# TamaCollar1_Mk1_Schematic_v34_V45.net
KiCad netlist of a schematic drawn in EAGLE
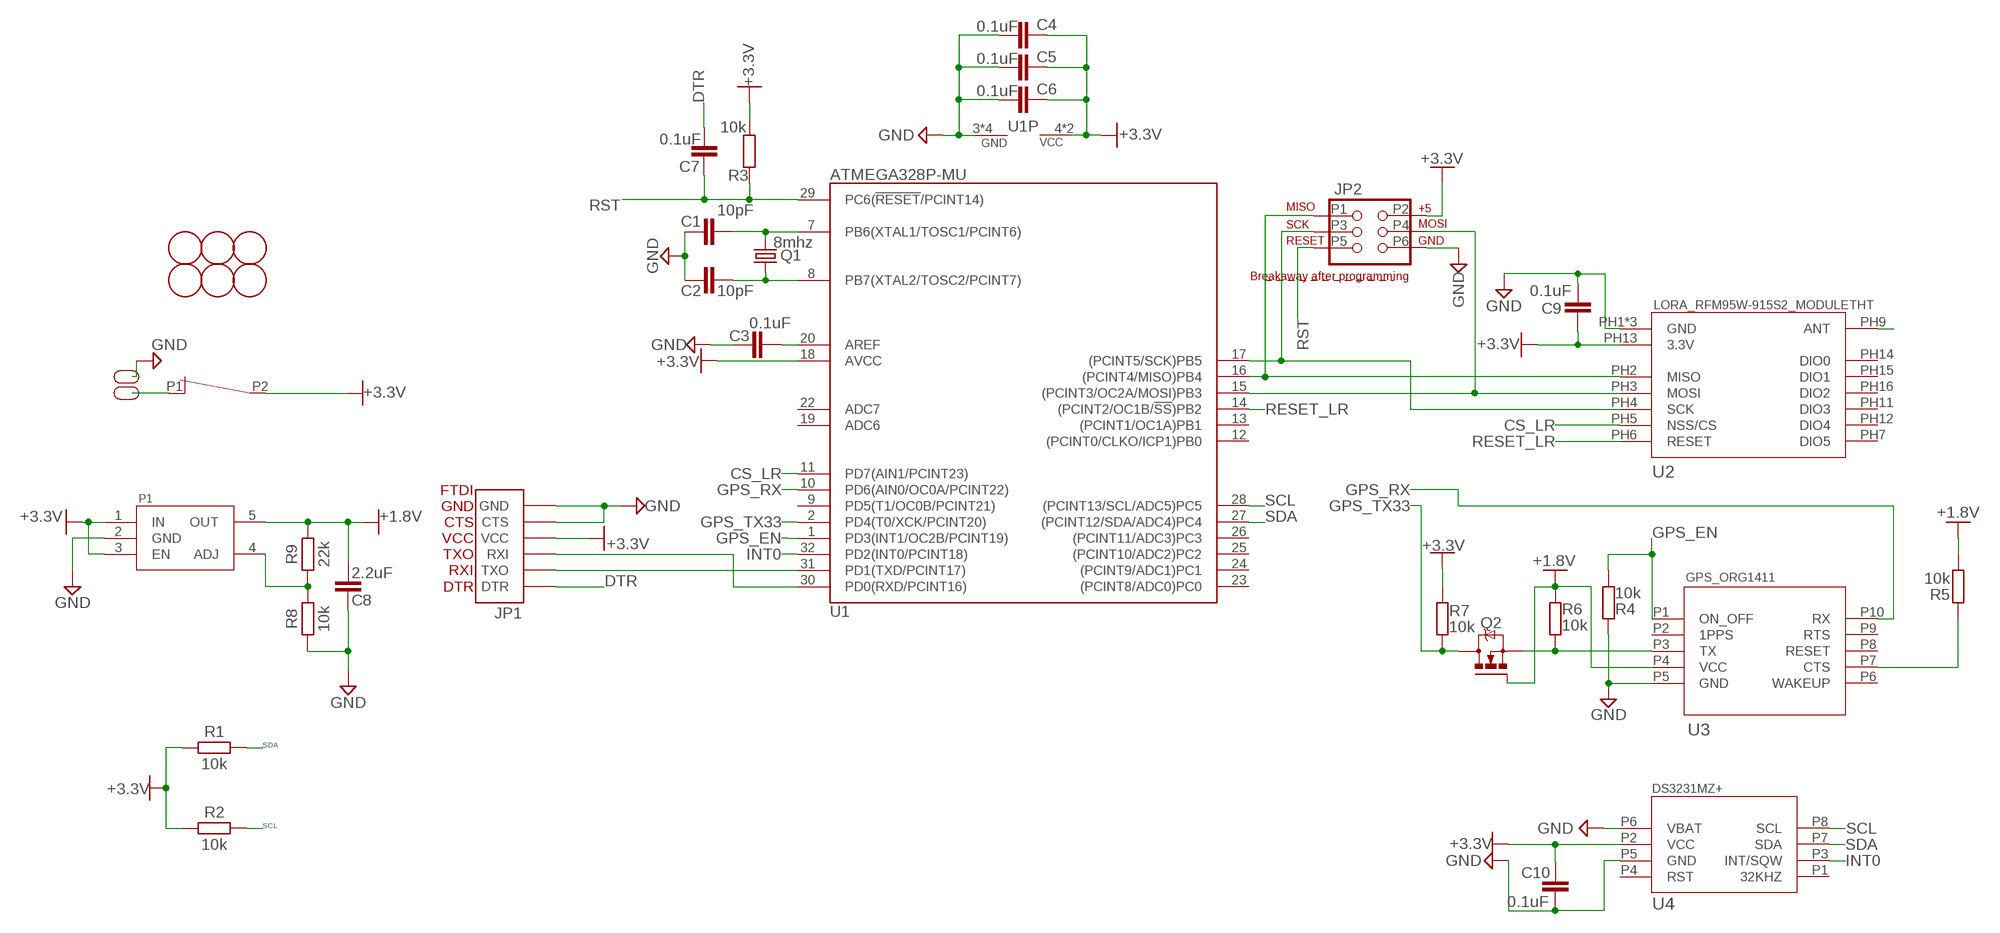
[diagram p0: schematic, sheet 1]

(export (version "E")
  (design (tool "Eeschema 10.0.6"))
  (components
    (comp (ref "BATT+")
      (value "BREAKOUT_PADL")
      (footprint "eagle-import:BREAKOUT_PAD_1_1X2MM")
      (libsource (lib "eagle-import") (part "BREAKOUT_PADL"))
    )
    (comp (ref "BR2")
      (value "MOUSEBITE3X1.25")
      (footprint "eagle-import:MOUSEBITE_3H_6TRACE(1.25MM)")
      (libsource (lib "eagle-import") (part "MOUSEBITE3X1.25"))
    )
    (comp (ref "C1")
      (value "10pF")
      (footprint "eagle-import:CAPC1005X60")
      (libsource (lib "eagle-import") (part "CCHIP-0402(1005-METRIC)_"))
    )
    (comp (ref "C2")
      (value "10pF")
      (footprint "eagle-import:CAPC1005X60")
      (libsource (lib "eagle-import") (part "CCHIP-0402(1005-METRIC)_"))
    )
    (comp (ref "C3")
      (value "0.1uF")
      (footprint "eagle-import:CAPC1005X60")
      (libsource (lib "eagle-import") (part "CCHIP-0402(1005-METRIC)_"))
    )
    (comp (ref "C4")
      (value "0.1uF")
      (footprint "eagle-import:CAPC1005X60")
      (libsource (lib "eagle-import") (part "CCHIP-0402(1005-METRIC)_"))
    )
    (comp (ref "C5")
      (value "0.1uF")
      (footprint "eagle-import:CAPC1005X60")
      (libsource (lib "eagle-import") (part "CCHIP-0402(1005-METRIC)_"))
    )
    (comp (ref "C6")
      (value "0.1uF")
      (footprint "eagle-import:CAPC1005X60")
      (libsource (lib "eagle-import") (part "CCHIP-0402(1005-METRIC)_"))
    )
    (comp (ref "C7")
      (value "0.1uF")
      (footprint "eagle-import:CAPC1005X60")
      (libsource (lib "eagle-import") (part "CCHIP-0402(1005-METRIC)_"))
    )
    (comp (ref "C8")
      (value "2.2uF")
      (footprint "eagle-import:CAPC1005X60")
      (libsource (lib "eagle-import") (part "CCHIP-0402(1005-METRIC)_"))
    )
    (comp (ref "C9")
      (value "0.1uF")
      (footprint "eagle-import:CAPC1005X60")
      (libsource (lib "eagle-import") (part "CCHIP-0402(1005-METRIC)_"))
    )
    (comp (ref "C10")
      (value "0.1uF")
      (footprint "eagle-import:CAPC1005X60")
      (libsource (lib "eagle-import") (part "CCHIP-0402(1005-METRIC)_"))
    )
    (comp (ref "F1")
      (value "FIDUCIAL")
      (footprint "eagle-import:FIDUCIAL_1MM")
      (libsource (lib "eagle-import") (part "FIDUCIAL"))
    )
    (comp (ref "F2")
      (value "FIDUCIAL")
      (footprint "eagle-import:FIDUCIAL_1MM")
      (libsource (lib "eagle-import") (part "FIDUCIAL"))
    )
    (comp (ref "F3")
      (value "FIDUCIAL")
      (footprint "eagle-import:FIDUCIAL_1MM")
      (libsource (lib "eagle-import") (part "FIDUCIAL"))
    )
    (comp (ref "F4")
      (value "FIDUCIAL")
      (footprint "eagle-import:FIDUCIAL_1MM")
      (libsource (lib "eagle-import") (part "FIDUCIAL"))
    )
    (comp (ref "F5")
      (value "FIDUCIAL")
      (footprint "eagle-import:FIDUCIAL_1MM")
      (libsource (lib "eagle-import") (part "FIDUCIAL"))
    )
    (comp (ref "F6")
      (value "FIDUCIAL")
      (footprint "eagle-import:FIDUCIAL_1MM")
      (libsource (lib "eagle-import") (part "FIDUCIAL"))
    )
    (comp (ref "GND")
      (value "BREAKOUT_PADL")
      (footprint "eagle-import:BREAKOUT_PAD_1_1X2MM")
      (libsource (lib "eagle-import") (part "BREAKOUT_PADL"))
    )
    (comp (ref "JP1")
      (value "FTDI_DEVICESMALL")
      (footprint "eagle-import:FTDI_DEVICE_SMD_SMALL")
      (libsource (lib "eagle-import") (part "FTDI_DEVICESMALL"))
    )
    (comp (ref "JP2")
      (value "AVR_SPI_PRG_61X6")
      (footprint "eagle-import:1X6-SMD")
      (libsource (lib "eagle-import") (part "AVR_SPI_PRG_61X6"))
    )
    (comp (ref "P1")
      (value "LDO_MIC5205YM5")
      (footprint "eagle-import:MIC5205")
      (libsource (lib "eagle-import") (part "LDO_MIC5205YM5"))
    )
    (comp (ref "Q1")
      (value "8mhz")
      (footprint "eagle-import:CRYSTAL_NX3225GD")
      (libsource (lib "eagle-import") (part "CRYSTAL"))
    )
    (comp (ref "Q2")
      (value "NMOSFET")
      (footprint "eagle-import:SOT23")
      (libsource (lib "eagle-import") (part "NMOSFETSOT23"))
    )
    (comp (ref "R1")
      (value "10k")
      (footprint "eagle-import:RESC1005X40")
      (libsource (lib "eagle-import") (part "RCHIP-0402(1005-METRIC)_"))
    )
    (comp (ref "R2")
      (value "10k")
      (footprint "eagle-import:RESC1005X40")
      (libsource (lib "eagle-import") (part "RCHIP-0402(1005-METRIC)_"))
    )
    (comp (ref "R3")
      (value "10k")
      (footprint "eagle-import:RESC1005X40")
      (libsource (lib "eagle-import") (part "RCHIP-0402(1005-METRIC)_"))
    )
    (comp (ref "R4")
      (value "10k")
      (footprint "eagle-import:RESC1005X40")
      (libsource (lib "eagle-import") (part "RCHIP-0402(1005-METRIC)_"))
    )
    (comp (ref "R5")
      (value "10k")
      (footprint "eagle-import:RESC1005X40")
      (libsource (lib "eagle-import") (part "RCHIP-0402(1005-METRIC)_"))
    )
    (comp (ref "R6")
      (value "10k")
      (footprint "eagle-import:RESC1005X40")
      (libsource (lib "eagle-import") (part "RCHIP-0402(1005-METRIC)_"))
    )
    (comp (ref "R7")
      (value "10k")
      (footprint "eagle-import:RESC1005X40")
      (libsource (lib "eagle-import") (part "RCHIP-0402(1005-METRIC)_"))
    )
    (comp (ref "R8")
      (value "10k")
      (footprint "eagle-import:RESC1005X40")
      (libsource (lib "eagle-import") (part "RCHIP-0402(1005-METRIC)_"))
    )
    (comp (ref "R9")
      (value "22k")
      (footprint "eagle-import:RESC1005X40")
      (libsource (lib "eagle-import") (part "RCHIP-0402(1005-METRIC)_"))
    )
    (comp (ref "SW1")
      (value "REED_SWITCH")
      (footprint "eagle-import:REED_CT05")
      (libsource (lib "eagle-import") (part "REED_SWITCH"))
    )
    (comp (ref "U1")
      (value "ATMEGA328P-MU")
      (footprint "eagle-import:QFN32_5X5_0.50")
      (fields
        (field (name "LINK") "https://www.rhydolabz.com/components-microcontrollers-c-172_192/atmega328pmu-smd-p-2612.html")
      )
      (libsource (lib "eagle-import") (part "ATMEGA8P-MU32"))
    )
    (comp (ref "U2")
      (value "LORA_RFM95W-915S2_MODULETHT")
      (footprint "eagle-import:LORA_RFM95W-915S2_16STANDOFFMODULE")
      (libsource (lib "eagle-import") (part "LORA_RFM95W-915S2_MODULETHT"))
    )
    (comp (ref "U3")
      (value "GPS_ORG1411")
      (footprint "eagle-import:ORG1411")
      (libsource (lib "eagle-import") (part "GPS_ORG1411"))
    )
    (comp (ref "U4")
      (value "DS3231MZ+")
      (footprint "eagle-import:DS3231MZ+_SOIC8")
      (libsource (lib "eagle-import") (part "DS3231MZ+"))
    )
  )
  (nets
    (net (code "1") (name "+1.8V") (class "Default")
      (node (ref "C8") (pin "2") (pinfunction "2_2") (pintype "passive"))
      (node (ref "P1") (pin "5") (pinfunction "OUT_5") (pintype "bidirectional"))
      (node (ref "Q2") (pin "1") (pinfunction "G_1") (pintype "passive"))
      (node (ref "R5") (pin "1") (pinfunction "1_1") (pintype "passive"))
      (node (ref "R6") (pin "2") (pinfunction "2_2") (pintype "passive"))
      (node (ref "R9") (pin "2") (pinfunction "2_2") (pintype "passive"))
      (node (ref "U3") (pin "P4") (pinfunction "VCC_P4") (pintype "power_in"))
    )
    (net (code "2") (name "+3.3V") (class "Default")
      (node (ref "C10") (pin "1") (pinfunction "1_1") (pintype "passive"))
      (node (ref "C4") (pin "1") (pinfunction "1_1") (pintype "passive"))
      (node (ref "C5") (pin "1") (pinfunction "1_1") (pintype "passive"))
      (node (ref "C6") (pin "1") (pinfunction "1_1") (pintype "passive"))
      (node (ref "C9") (pin "1") (pinfunction "1_1") (pintype "passive"))
      (node (ref "JP1") (pin "P4") (pinfunction "VCC_P4") (pintype "bidirectional"))
      (node (ref "JP2") (pin "P2") (pinfunction "2_P2") (pintype "passive"))
      (node (ref "P1") (pin "1") (pinfunction "IN_1") (pintype "bidirectional"))
      (node (ref "P1") (pin "3") (pinfunction "EN_3") (pintype "bidirectional"))
      (node (ref "R1") (pin "1") (pinfunction "1_1") (pintype "passive"))
      (node (ref "R2") (pin "1") (pinfunction "1_1") (pintype "passive"))
      (node (ref "R3") (pin "1") (pinfunction "1_1") (pintype "passive"))
      (node (ref "R7") (pin "2") (pinfunction "2_2") (pintype "passive"))
      (node (ref "SW1") (pin "P2") (pinfunction "PAD2_P2") (pintype "bidirectional"))
      (node (ref "U1") (pin "18") (pinfunction "AVCC_18") (pintype "power_in"))
      (node (ref "U1") (pin "4") (pinfunction "VCC_4") (pintype "power_in"))
      (node (ref "U1") (pin "6") (pinfunction "VCC_6") (pintype "power_in"))
      (node (ref "U2") (pin "PH13") (pinfunction "3.3V_PH13") (pintype "bidirectional"))
      (node (ref "U4") (pin "P2") (pinfunction "VCC_P2") (pintype "power_in"))
    )
    (net (code "3") (name "/CS_LR") (class "Default")
      (node (ref "U1") (pin "11") (pinfunction "PD7(AIN1/PCINT23)_11") (pintype "bidirectional"))
      (node (ref "U2") (pin "PH5") (pinfunction "NSS/CS_PH5") (pintype "bidirectional"))
    )
    (net (code "4") (name "/DTR") (class "Default")
      (node (ref "C7") (pin "2") (pinfunction "2_2") (pintype "passive"))
      (node (ref "JP1") (pin "P1") (pinfunction "DTR_P1") (pintype "bidirectional"))
    )
    (net (code "5") (name "/GPS_EN") (class "Default")
      (node (ref "R4") (pin "1") (pinfunction "1_1") (pintype "passive"))
      (node (ref "U1") (pin "1") (pinfunction "PD3(INT1/OC2B/PCINT19)_1") (pintype "bidirectional"))
      (node (ref "U3") (pin "P1") (pinfunction "ON_OFF_P1") (pintype "input"))
    )
    (net (code "6") (name "/GPS_RX") (class "Default")
      (node (ref "U1") (pin "10") (pinfunction "PD6(AIN0/OC0A/PCINT22)_10") (pintype "bidirectional"))
      (node (ref "U3") (pin "P10") (pinfunction "RX_P10") (pintype "bidirectional"))
    )
    (net (code "7") (name "/GPS_TX33") (class "Default")
      (node (ref "Q2") (pin "3") (pinfunction "D_3") (pintype "passive"))
      (node (ref "R7") (pin "1") (pinfunction "1_1") (pintype "passive"))
      (node (ref "U1") (pin "2") (pinfunction "PD4(T0/XCK/PCINT20)_2") (pintype "bidirectional"))
    )
    (net (code "8") (name "/INT0") (class "Default")
      (node (ref "U1") (pin "32") (pinfunction "PD2(INT0/PCINT18)_32") (pintype "bidirectional"))
      (node (ref "U4") (pin "P3") (pinfunction "INT/SQW_P3") (pintype "bidirectional"))
    )
    (net (code "9") (name "/RESET_LR") (class "Default")
      (node (ref "U1") (pin "14") (pinfunction "(PCINT2/OC1B/~{SS})PB2_14") (pintype "bidirectional"))
      (node (ref "U2") (pin "PH6") (pinfunction "RESET_PH6") (pintype "bidirectional"))
    )
    (net (code "10") (name "/RST") (class "Default")
      (node (ref "C7") (pin "1") (pinfunction "1_1") (pintype "passive"))
      (node (ref "JP2") (pin "P5") (pinfunction "5_P5") (pintype "passive"))
      (node (ref "R3") (pin "2") (pinfunction "2_2") (pintype "passive"))
      (node (ref "U1") (pin "29") (pinfunction "PC6(~{RESET}/PCINT14)_29") (pintype "bidirectional"))
    )
    (net (code "11") (name "/SCL") (class "Default")
      (node (ref "R2") (pin "2") (pinfunction "2_2") (pintype "passive"))
      (node (ref "U1") (pin "28") (pinfunction "(PCINT13/SCL/ADC5)PC5_28") (pintype "bidirectional"))
      (node (ref "U4") (pin "P8") (pinfunction "SCL_P8") (pintype "bidirectional"))
    )
    (net (code "12") (name "/SDA") (class "Default")
      (node (ref "R1") (pin "2") (pinfunction "2_2") (pintype "passive"))
      (node (ref "U1") (pin "27") (pinfunction "(PCINT12/SDA/ADC4)PC4_27") (pintype "bidirectional"))
      (node (ref "U4") (pin "P7") (pinfunction "SDA_P7") (pintype "bidirectional"))
    )
    (net (code "13") (name "GND") (class "Default")
      (node (ref "C1") (pin "1") (pinfunction "1_1") (pintype "passive"))
      (node (ref "C10") (pin "2") (pinfunction "2_2") (pintype "passive"))
      (node (ref "C2") (pin "1") (pinfunction "1_1") (pintype "passive"))
      (node (ref "C3") (pin "1") (pinfunction "1_1") (pintype "passive"))
      (node (ref "C4") (pin "2") (pinfunction "2_2") (pintype "passive"))
      (node (ref "C5") (pin "2") (pinfunction "2_2") (pintype "passive"))
      (node (ref "C6") (pin "2") (pinfunction "2_2") (pintype "passive"))
      (node (ref "C8") (pin "1") (pinfunction "1_1") (pintype "passive"))
      (node (ref "C9") (pin "2") (pinfunction "2_2") (pintype "passive"))
      (node (ref "GND") (pin "P$1") (pinfunction "P$1_P$1") (pintype "bidirectional"))
      (node (ref "JP1") (pin "P5") (pinfunction "CTS_P5") (pintype "bidirectional"))
      (node (ref "JP1") (pin "P6") (pinfunction "GND_P6") (pintype "bidirectional"))
      (node (ref "JP2") (pin "P6") (pinfunction "6_P6") (pintype "passive"))
      (node (ref "P1") (pin "2") (pinfunction "GND_2") (pintype "bidirectional"))
      (node (ref "R4") (pin "2") (pinfunction "2_2") (pintype "passive"))
      (node (ref "R8") (pin "1") (pinfunction "1_1") (pintype "passive"))
      (node (ref "U1") (pin "21") (pinfunction "GND_21") (pintype "power_in"))
      (node (ref "U1") (pin "3") (pinfunction "GND_3") (pintype "power_in"))
      (node (ref "U1") (pin "5") (pinfunction "GND_5") (pintype "power_in"))
      (node (ref "U1") (pin "EXP") (pinfunction "GND_EXP") (pintype "power_in"))
      (node (ref "U2") (pin "PH1") (pinfunction "GND_PH1") (pintype "bidirectional"))
      (node (ref "U2") (pin "PH10") (pinfunction "GND_PH10") (pintype "bidirectional"))
      (node (ref "U2") (pin "PH8") (pinfunction "GND_PH8") (pintype "bidirectional"))
      (node (ref "U3") (pin "P5") (pinfunction "GND_P5") (pintype "power_in"))
      (node (ref "U4") (pin "P5") (pinfunction "GND_P5") (pintype "power_in"))
      (node (ref "U4") (pin "P6") (pinfunction "VBAT_P6") (pintype "power_in"))
    )
    (net (code "14") (name "Net-(JP1-RXI)") (class "Default")
      (node (ref "JP1") (pin "P3") (pinfunction "RXI_P3") (pintype "bidirectional"))
      (node (ref "U1") (pin "30") (pinfunction "PD0(RXD/PCINT16)_30") (pintype "bidirectional"))
    )
    (net (code "15") (name "Net-(JP1-TXO)") (class "Default")
      (node (ref "JP1") (pin "P2") (pinfunction "TXO_P2") (pintype "bidirectional"))
      (node (ref "U1") (pin "31") (pinfunction "PD1(TXD/PCINT17)_31") (pintype "bidirectional"))
    )
    (net (code "16") (name "Net-(JP2-1)") (class "Default")
      (node (ref "JP2") (pin "P1") (pinfunction "1_P1") (pintype "passive"))
      (node (ref "U1") (pin "16") (pinfunction "(PCINT4/MISO)PB4_16") (pintype "bidirectional"))
      (node (ref "U2") (pin "PH2") (pinfunction "MISO_PH2") (pintype "bidirectional"))
    )
    (net (code "17") (name "Net-(JP2-3)") (class "Default")
      (node (ref "JP2") (pin "P3") (pinfunction "3_P3") (pintype "passive"))
      (node (ref "U1") (pin "17") (pinfunction "(PCINT5/SCK)PB5_17") (pintype "bidirectional"))
      (node (ref "U2") (pin "PH4") (pinfunction "SCK_PH4") (pintype "bidirectional"))
    )
    (net (code "18") (name "Net-(JP2-4)") (class "Default")
      (node (ref "JP2") (pin "P4") (pinfunction "4_P4") (pintype "passive"))
      (node (ref "U1") (pin "15") (pinfunction "(PCINT3/OC2A/MOSI)PB3_15") (pintype "bidirectional"))
      (node (ref "U2") (pin "PH3") (pinfunction "MOSI_PH3") (pintype "bidirectional"))
    )
    (net (code "19") (name "Net-(P1-ADJ)") (class "Default")
      (node (ref "P1") (pin "4") (pinfunction "ADJ_4") (pintype "bidirectional"))
      (node (ref "R8") (pin "2") (pinfunction "2_2") (pintype "passive"))
      (node (ref "R9") (pin "1") (pinfunction "1_1") (pintype "passive"))
    )
    (net (code "20") (name "Net-(Q1-1)") (class "Default")
      (node (ref "C2") (pin "2") (pinfunction "2_2") (pintype "passive"))
      (node (ref "Q1") (pin "P1") (pinfunction "1_P1") (pintype "passive"))
      (node (ref "U1") (pin "8") (pinfunction "PB7(XTAL2/TOSC2/PCINT7)_8") (pintype "bidirectional"))
    )
    (net (code "21") (name "Net-(Q1-2)") (class "Default")
      (node (ref "C1") (pin "2") (pinfunction "2_2") (pintype "passive"))
      (node (ref "Q1") (pin "P2") (pinfunction "2_P2") (pintype "passive"))
      (node (ref "U1") (pin "7") (pinfunction "PB6(XTAL1/TOSC1/PCINT6)_7") (pintype "bidirectional"))
    )
    (net (code "22") (name "Net-(Q2-S)") (class "Default")
      (node (ref "Q2") (pin "2") (pinfunction "S_2") (pintype "passive"))
      (node (ref "R6") (pin "1") (pinfunction "1_1") (pintype "passive"))
      (node (ref "U3") (pin "P3") (pinfunction "TX_P3") (pintype "bidirectional"))
    )
    (net (code "23") (name "Net-(SW1-PAD1)") (class "Default")
      (node (ref "BATT+") (pin "P$1") (pinfunction "P$1_P$1") (pintype "bidirectional"))
      (node (ref "SW1") (pin "P1") (pinfunction "PAD1_P1") (pintype "bidirectional"))
    )
    (net (code "24") (name "Net-(U1A-AREF)") (class "Default")
      (node (ref "C3") (pin "2") (pinfunction "2_2") (pintype "passive"))
      (node (ref "U1") (pin "20") (pinfunction "AREF_20") (pintype "passive"))
    )
    (net (code "25") (name "Net-(U3-CTS)") (class "Default")
      (node (ref "R5") (pin "2") (pinfunction "2_2") (pintype "passive"))
      (node (ref "U3") (pin "P7") (pinfunction "CTS_P7") (pintype "bidirectional"))
    )
    (net (code "26") (name "unconnected-(U1A-(PCINT0{slash}CLKO{slash}ICP1)PB0-Pad12)") (class "Default")
      (node (ref "U1") (pin "12") (pinfunction "(PCINT0/CLKO/ICP1)PB0_12") (pintype "bidirectional"))
    )
    (net (code "27") (name "unconnected-(U1A-(PCINT1{slash}OC1A)PB1-Pad13)") (class "Default")
      (node (ref "U1") (pin "13") (pinfunction "(PCINT1/OC1A)PB1_13") (pintype "bidirectional"))
    )
    (net (code "28") (name "unconnected-(U1A-(PCINT8{slash}ADC0)PC0-Pad23)") (class "Default")
      (node (ref "U1") (pin "23") (pinfunction "(PCINT8/ADC0)PC0_23") (pintype "bidirectional"))
    )
    (net (code "29") (name "unconnected-(U1A-(PCINT9{slash}ADC1)PC1-Pad24)") (class "Default")
      (node (ref "U1") (pin "24") (pinfunction "(PCINT9/ADC1)PC1_24") (pintype "bidirectional"))
    )
    (net (code "30") (name "unconnected-(U1A-(PCINT10{slash}ADC2)PC2-Pad25)") (class "Default")
      (node (ref "U1") (pin "25") (pinfunction "(PCINT10/ADC2)PC2_25") (pintype "bidirectional"))
    )
    (net (code "31") (name "unconnected-(U1A-(PCINT11{slash}ADC3)PC3-Pad26)") (class "Default")
      (node (ref "U1") (pin "26") (pinfunction "(PCINT11/ADC3)PC3_26") (pintype "bidirectional"))
    )
    (net (code "32") (name "unconnected-(U1A-ADC6-Pad19)") (class "Default")
      (node (ref "U1") (pin "19") (pinfunction "ADC6_19") (pintype "bidirectional"))
    )
    (net (code "33") (name "unconnected-(U1A-ADC7-Pad22)") (class "Default")
      (node (ref "U1") (pin "22") (pinfunction "ADC7_22") (pintype "bidirectional"))
    )
    (net (code "34") (name "unconnected-(U1A-PD5(T1{slash}OC0B{slash}PCINT21)-Pad9)") (class "Default")
      (node (ref "U1") (pin "9") (pinfunction "PD5(T1/OC0B/PCINT21)_9") (pintype "bidirectional"))
    )
    (net (code "35") (name "unconnected-(U2-ANT-PadPH9)") (class "Default")
      (node (ref "U2") (pin "PH9") (pinfunction "ANT_PH9") (pintype "bidirectional"))
    )
    (net (code "36") (name "unconnected-(U2-DIO0-PadPH14)") (class "Default")
      (node (ref "U2") (pin "PH14") (pinfunction "DIO0_PH14") (pintype "bidirectional"))
    )
    (net (code "37") (name "unconnected-(U2-DIO1-PadPH15)") (class "Default")
      (node (ref "U2") (pin "PH15") (pinfunction "DIO1_PH15") (pintype "bidirectional"))
    )
    (net (code "38") (name "unconnected-(U2-DIO2-PadPH16)") (class "Default")
      (node (ref "U2") (pin "PH16") (pinfunction "DIO2_PH16") (pintype "bidirectional"))
    )
    (net (code "39") (name "unconnected-(U2-DIO3-PadPH11)") (class "Default")
      (node (ref "U2") (pin "PH11") (pinfunction "DIO3_PH11") (pintype "bidirectional"))
    )
    (net (code "40") (name "unconnected-(U2-DIO4-PadPH12)") (class "Default")
      (node (ref "U2") (pin "PH12") (pinfunction "DIO4_PH12") (pintype "bidirectional"))
    )
    (net (code "41") (name "unconnected-(U2-DIO5-PadPH7)") (class "Default")
      (node (ref "U2") (pin "PH7") (pinfunction "DIO5_PH7") (pintype "bidirectional"))
    )
    (net (code "42") (name "unconnected-(U3-1PPS-PadP2)") (class "Default")
      (node (ref "U3") (pin "P2") (pinfunction "1PPS_P2") (pintype "output"))
    )
    (net (code "43") (name "unconnected-(U3-RESET-PadP8)") (class "Default")
      (node (ref "U3") (pin "P8") (pinfunction "RESET_P8") (pintype "input"))
    )
    (net (code "44") (name "unconnected-(U3-RTS-PadP9)") (class "Default")
      (node (ref "U3") (pin "P9") (pinfunction "RTS_P9") (pintype "bidirectional"))
    )
    (net (code "45") (name "unconnected-(U3-WAKEUP-PadP6)") (class "Default")
      (node (ref "U3") (pin "P6") (pinfunction "WAKEUP_P6") (pintype "output"))
    )
    (net (code "46") (name "unconnected-(U4-32KHZ-PadP1)") (class "Default")
      (node (ref "U4") (pin "P1") (pinfunction "32KHZ_P1") (pintype "bidirectional"))
    )
    (net (code "47") (name "unconnected-(U4-RST-PadP4)") (class "Default")
      (node (ref "U4") (pin "P4") (pinfunction "RST_P4") (pintype "bidirectional"))
    )
  )
)
